# AD8336.net
KiCad netlist of a schematic drawn in EasyEDA Pro
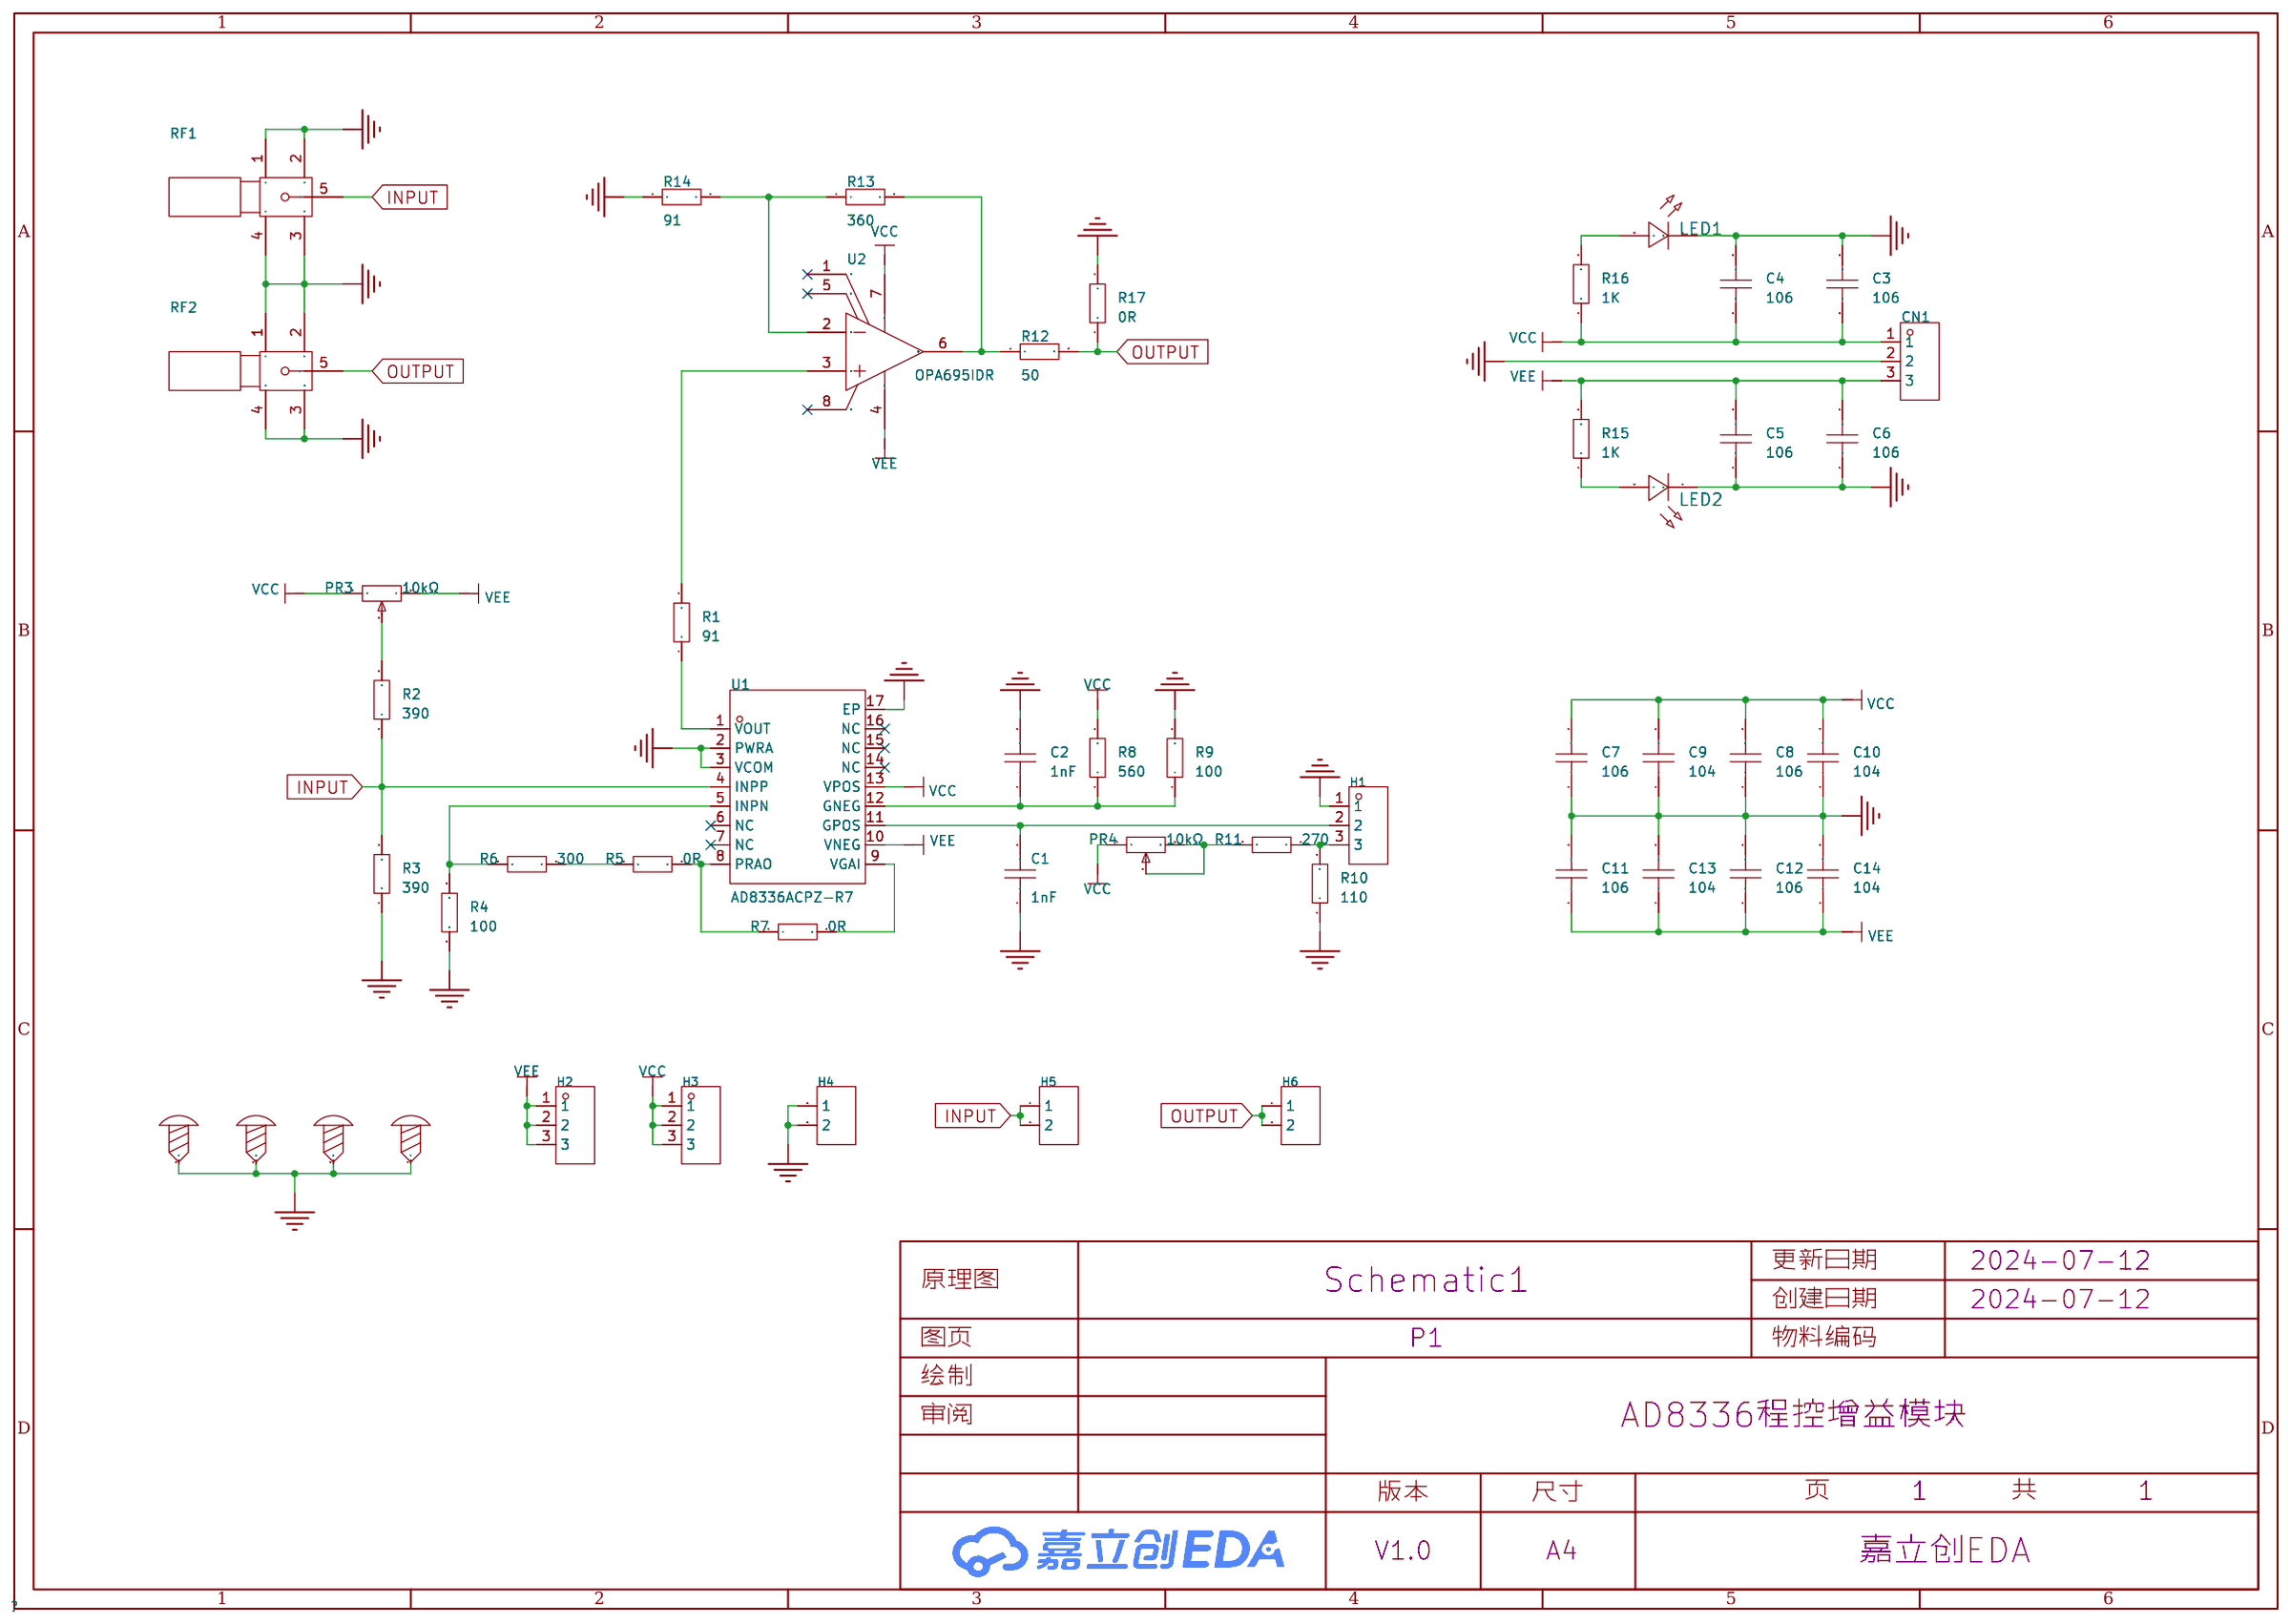
[diagram p0: schematic sheet]

(export (version "E")
  (design (tool "Eeschema 10.0.6"))
  (components
    (comp (ref "C1")
      (value "1nF")
      (footprint "easyedapro:C0603")
      (libsource (lib "easyedapro") (part "CapAcitance"))
    )
    (comp (ref "C2")
      (value "1nF")
      (footprint "easyedapro:C0603")
      (libsource (lib "easyedapro") (part "CapAcitance"))
    )
    (comp (ref "C3")
      (value "106")
      (footprint "easyedapro:C0603")
      (libsource (lib "easyedapro") (part "CapAcitance"))
    )
    (comp (ref "C4")
      (value "106")
      (footprint "easyedapro:C0603")
      (libsource (lib "easyedapro") (part "CapAcitance"))
    )
    (comp (ref "C5")
      (value "106")
      (footprint "easyedapro:C0603")
      (libsource (lib "easyedapro") (part "CapAcitance"))
    )
    (comp (ref "C6")
      (value "106")
      (footprint "easyedapro:C0603")
      (libsource (lib "easyedapro") (part "CapAcitance"))
    )
    (comp (ref "C7")
      (value "106")
      (footprint "easyedapro:C0603")
      (libsource (lib "easyedapro") (part "CapAcitance"))
    )
    (comp (ref "C8")
      (value "106")
      (footprint "easyedapro:C0603")
      (libsource (lib "easyedapro") (part "CapAcitance"))
    )
    (comp (ref "C9")
      (value "104")
      (footprint "easyedapro:C0603")
      (libsource (lib "easyedapro") (part "CapAcitance"))
    )
    (comp (ref "C10")
      (value "104")
      (footprint "easyedapro:C0603")
      (libsource (lib "easyedapro") (part "CapAcitance"))
    )
    (comp (ref "C11")
      (value "106")
      (footprint "easyedapro:C0603")
      (libsource (lib "easyedapro") (part "CapAcitance"))
    )
    (comp (ref "C12")
      (value "106")
      (footprint "easyedapro:C0603")
      (libsource (lib "easyedapro") (part "CapAcitance"))
    )
    (comp (ref "C13")
      (value "104")
      (footprint "easyedapro:C0603")
      (libsource (lib "easyedapro") (part "CapAcitance"))
    )
    (comp (ref "C14")
      (value "104")
      (footprint "easyedapro:C0603")
      (libsource (lib "easyedapro") (part "CapAcitance"))
    )
    (comp (ref "CN1")
      (value "MX301-5.0-03P-BU01-Cu-Y-A")
      (footprint "easyedapro:CONN-TH_3P-P5.0-MX301-5.0-03P-BU01-CU-Y-A")
      (fields (field (name "Manufacturer") "MAX(迈旭)"))
      (libsource (lib "easyedapro") (part "MX301-5.0-03P-BU01-CU-Y-A"))
    )
    (comp (ref "H1")
      (value "~")
      (footprint "easyedapro:HDR-TH_3P-P2.54-V-F")
      (libsource (lib "easyedapro") (part "PM254V-11-03-H85"))
    )
    (comp (ref "H2")
      (value "~")
      (footprint "easyedapro:HDR-TH_3P-P2.54-V-F")
      (libsource (lib "easyedapro") (part "PM254V-11-03-H85"))
    )
    (comp (ref "H3")
      (value "~")
      (footprint "easyedapro:HDR-TH_3P-P2.54-V-F")
      (libsource (lib "easyedapro") (part "PM254V-11-03-H85"))
    )
    (comp (ref "H4")
      (value "~")
      (footprint "easyedapro:HDR-TH_2P-P2.54-V-F")
      (libsource (lib "easyedapro") (part "Header-Female-2.54_1x2"))
    )
    (comp (ref "H5")
      (value "~")
      (footprint "easyedapro:HDR-TH_2P-P2.54-V-F")
      (libsource (lib "easyedapro") (part "Header-Female-2.54_1x2"))
    )
    (comp (ref "H6")
      (value "~")
      (footprint "easyedapro:HDR-TH_2P-P2.54-V-F")
      (libsource (lib "easyedapro") (part "Header-Female-2.54_1x2"))
    )
    (comp (ref "LED1")
      (value "~")
      (footprint "easyedapro:LED_0603")
      (libsource (lib "easyedapro") (part "LED_R"))
    )
    (comp (ref "LED2")
      (value "~")
      (footprint "easyedapro:LED_0603")
      (libsource (lib "easyedapro") (part "LED_R"))
    )
    (comp (ref "PR3")
      (value "10kΩ")
      (footprint "easyedapro:R_3296")
      (libsource (lib "easyedapro") (part "R_3296"))
    )
    (comp (ref "PR4")
      (value "10kΩ")
      (footprint "easyedapro:R_3296")
      (libsource (lib "easyedapro") (part "R_3296"))
    )
    (comp (ref "R1") (value "91") (footprint "easyedapro:R0603") (libsource (lib "easyedapro") (part "电阻")))
    (comp (ref "R2") (value "390") (footprint "easyedapro:R0603") (libsource (lib "easyedapro") (part "电阻")))
    (comp (ref "R3") (value "390") (footprint "easyedapro:R0603") (libsource (lib "easyedapro") (part "电阻")))
    (comp (ref "R4") (value "100") (footprint "easyedapro:R0603") (libsource (lib "easyedapro") (part "电阻")))
    (comp (ref "R5") (value "0R") (footprint "easyedapro:R0603") (libsource (lib "easyedapro") (part "电阻")))
    (comp (ref "R6") (value "300") (footprint "easyedapro:R0603") (libsource (lib "easyedapro") (part "电阻")))
    (comp (ref "R7") (value "0R") (footprint "easyedapro:R0603") (libsource (lib "easyedapro") (part "电阻")))
    (comp (ref "R8") (value "560") (footprint "easyedapro:R0603") (libsource (lib "easyedapro") (part "电阻")))
    (comp (ref "R9") (value "100") (footprint "easyedapro:R0603") (libsource (lib "easyedapro") (part "电阻")))
    (comp (ref "R10") (value "110") (footprint "easyedapro:R0603") (libsource (lib "easyedapro") (part "电阻")))
    (comp (ref "R11") (value "270") (footprint "easyedapro:R0603") (libsource (lib "easyedapro") (part "电阻")))
    (comp (ref "R12") (value "50") (footprint "easyedapro:R0603") (libsource (lib "easyedapro") (part "电阻")))
    (comp (ref "R13") (value "360") (footprint "easyedapro:R0603") (libsource (lib "easyedapro") (part "电阻")))
    (comp (ref "R14") (value "91") (footprint "easyedapro:R0603") (libsource (lib "easyedapro") (part "电阻")))
    (comp (ref "R15") (value "1K") (footprint "easyedapro:R0603") (libsource (lib "easyedapro") (part "电阻")))
    (comp (ref "R16") (value "1K") (footprint "easyedapro:R0603") (libsource (lib "easyedapro") (part "电阻")))
    (comp (ref "R17") (value "0R") (footprint "easyedapro:R0603") (libsource (lib "easyedapro") (part "电阻")))
    (comp (ref "RF1")
      (value "BWSMA-KE-Z001")
      (footprint "easyedapro:SMA-TH_BWSMA-KE-Z001")
      (fields (field (name "Manufacturer") "BAT WIRELESS(蝙蝠无线)"))
      (libsource (lib "easyedapro") (part "BWSMA-KE-Z001"))
    )
    (comp (ref "RF2")
      (value "BWSMA-KE-Z001")
      (footprint "easyedapro:SMA-TH_BWSMA-KE-Z001")
      (fields (field (name "Manufacturer") "BAT WIRELESS(蝙蝠无线)"))
      (libsource (lib "easyedapro") (part "BWSMA-KE-Z001"))
    )
    (comp (ref "TP1") (value "~") (footprint "easyedapro:M3螺丝") (libsource (lib "easyedapro") (part "螺丝孔")))
    (comp (ref "TP2") (value "~") (footprint "easyedapro:M3螺丝") (libsource (lib "easyedapro") (part "螺丝孔")))
    (comp (ref "TP3") (value "~") (footprint "easyedapro:M3螺丝") (libsource (lib "easyedapro") (part "螺丝孔")))
    (comp (ref "TP4") (value "~") (footprint "easyedapro:M3螺丝") (libsource (lib "easyedapro") (part "螺丝孔")))
    (comp (ref "U1")
      (value "AD8336ACPZ-R7")
      (footprint "easyedapro:LFCSP-16_L4.0-W4.0-P0.65-BL-EP2.2")
      (description "可变增益放大器-IC-信号处理-16-LFCSP-VQ（4x4）")
      (fields (field (name "Manufacturer") "ADI(亚德诺)"))
      (libsource (lib "easyedapro") (part "AD8336ACPZ-R7"))
    )
    (comp (ref "U2")
      (value "OPA695IDR")
      (footprint "easyedapro:SOIC-8_L5.0-W4.0-P1.27-LS6.1-BL")
      (description "放大器数:单路;增益带宽积(GBP):-;输入偏置电流(Ib):20uA;压摆率(SR):4300V/us;带宽(-3db):1.7GHz;")
      (fields (field (name "Manufacturer") "TI(德州仪器)"))
      (libsource (lib "easyedapro") (part "OPA695IDR"))
    )
  )
  (nets
    (net (code "1") (name "GND") (class "Default")
      (node (ref "C1") (pin "1") (pinfunction "1_1") (pintype "input"))
      (node (ref "C10") (pin "1") (pinfunction "1_1") (pintype "input"))
      (node (ref "C11") (pin "2") (pinfunction "2_2") (pintype "input"))
      (node (ref "C12") (pin "2") (pinfunction "2_2") (pintype "input"))
      (node (ref "C13") (pin "2") (pinfunction "2_2") (pintype "input"))
      (node (ref "C14") (pin "2") (pinfunction "2_2") (pintype "input"))
      (node (ref "C2") (pin "2") (pinfunction "2_2") (pintype "input"))
      (node (ref "C3") (pin "2") (pinfunction "2_2") (pintype "input"))
      (node (ref "C4") (pin "2") (pinfunction "2_2") (pintype "input"))
      (node (ref "C5") (pin "1") (pinfunction "1_1") (pintype "input"))
      (node (ref "C6") (pin "1") (pinfunction "1_1") (pintype "input"))
      (node (ref "C7") (pin "1") (pinfunction "1_1") (pintype "input"))
      (node (ref "C8") (pin "1") (pinfunction "1_1") (pintype "input"))
      (node (ref "C9") (pin "1") (pinfunction "1_1") (pintype "input"))
      (node (ref "CN1") (pin "2") (pinfunction "2_2") (pintype "unspecified"))
      (node (ref "H1") (pin "1") (pinfunction "1_1") (pintype "input"))
      (node (ref "H4") (pin "1") (pinfunction "1_1") (pintype "input"))
      (node (ref "H4") (pin "2") (pinfunction "2_2") (pintype "input"))
      (node (ref "LED1") (pin "1") (pinfunction "C_1") (pintype "input"))
      (node (ref "LED2") (pin "1") (pinfunction "C_1") (pintype "input"))
      (node (ref "R10") (pin "1") (pinfunction "1_1") (pintype "input"))
      (node (ref "R14") (pin "1") (pinfunction "1_1") (pintype "input"))
      (node (ref "R17") (pin "2") (pinfunction "2_2") (pintype "input"))
      (node (ref "R3") (pin "1") (pinfunction "1_1") (pintype "input"))
      (node (ref "R4") (pin "1") (pinfunction "1_1") (pintype "input"))
      (node (ref "R9") (pin "2") (pinfunction "2_2") (pintype "input"))
      (node (ref "RF1") (pin "1") (pinfunction "1_1") (pintype "unspecified"))
      (node (ref "RF1") (pin "2") (pinfunction "2_2") (pintype "unspecified"))
      (node (ref "RF1") (pin "3") (pinfunction "3_3") (pintype "unspecified"))
      (node (ref "RF1") (pin "4") (pinfunction "4_4") (pintype "unspecified"))
      (node (ref "RF2") (pin "1") (pinfunction "1_1") (pintype "unspecified"))
      (node (ref "RF2") (pin "2") (pinfunction "2_2") (pintype "unspecified"))
      (node (ref "RF2") (pin "3") (pinfunction "3_3") (pintype "unspecified"))
      (node (ref "RF2") (pin "4") (pinfunction "4_4") (pintype "unspecified"))
      (node (ref "TP1") (pin "1") (pinfunction "1_1") (pintype "input"))
      (node (ref "TP2") (pin "1") (pinfunction "1_1") (pintype "input"))
      (node (ref "TP3") (pin "1") (pinfunction "1_1") (pintype "input"))
      (node (ref "TP4") (pin "1") (pinfunction "1_1") (pintype "input"))
      (node (ref "U1") (pin "17") (pinfunction "EP_17") (pintype "unspecified"))
      (node (ref "U1") (pin "2") (pinfunction "PWRA_2") (pintype "unspecified"))
      (node (ref "U1") (pin "3") (pinfunction "VCOM_3") (pintype "unspecified"))
    )
    (net (code "2") (name "INPUT") (class "Default")
      (node (ref "H5") (pin "1") (pinfunction "1_1") (pintype "input"))
      (node (ref "H5") (pin "2") (pinfunction "2_2") (pintype "input"))
      (node (ref "R2") (pin "1") (pinfunction "1_1") (pintype "input"))
      (node (ref "R3") (pin "2") (pinfunction "2_2") (pintype "input"))
      (node (ref "RF1") (pin "5") (pinfunction "5_5") (pintype "unspecified"))
      (node (ref "U1") (pin "4") (pinfunction "INPP_4") (pintype "unspecified"))
    )
    (net (code "3") (name "Net-(H1-Pad3)") (class "Default")
      (node (ref "H1") (pin "3") (pinfunction "3_3") (pintype "input"))
      (node (ref "R10") (pin "2") (pinfunction "2_2") (pintype "input"))
      (node (ref "R11") (pin "1") (pinfunction "1_1") (pintype "input"))
    )
    (net (code "4") (name "Net-(LED1-A)") (class "Default")
      (node (ref "LED1") (pin "2") (pinfunction "A_2") (pintype "input"))
      (node (ref "R16") (pin "2") (pinfunction "2_2") (pintype "input"))
    )
    (net (code "5") (name "Net-(LED2-A)") (class "Default")
      (node (ref "LED2") (pin "2") (pinfunction "A_2") (pintype "input"))
      (node (ref "R15") (pin "1") (pinfunction "1_1") (pintype "input"))
    )
    (net (code "6") (name "Net-(PR3-Pad2)") (class "Default")
      (node (ref "PR3") (pin "2") (pinfunction "2_2") (pintype "input"))
      (node (ref "R2") (pin "2") (pinfunction "2_2") (pintype "input"))
    )
    (net (code "7") (name "Net-(PR4-Pad2)") (class "Default")
      (node (ref "PR4") (pin "2") (pinfunction "2_2") (pintype "input"))
      (node (ref "PR4") (pin "3") (pinfunction "3_3") (pintype "input"))
      (node (ref "R11") (pin "2") (pinfunction "2_2") (pintype "input"))
    )
    (net (code "8") (name "Net-(R5-Pad1)") (class "Default")
      (node (ref "R5") (pin "1") (pinfunction "1_1") (pintype "input"))
      (node (ref "R6") (pin "2") (pinfunction "2_2") (pintype "input"))
    )
    (net (code "9") (name "Net-(U1-GNEG)") (class "Default")
      (node (ref "C2") (pin "1") (pinfunction "1_1") (pintype "input"))
      (node (ref "R8") (pin "1") (pinfunction "1_1") (pintype "input"))
      (node (ref "R9") (pin "1") (pinfunction "1_1") (pintype "input"))
      (node (ref "U1") (pin "12") (pinfunction "GNEG_12") (pintype "unspecified"))
    )
    (net (code "10") (name "Net-(U1-GPOS)") (class "Default")
      (node (ref "C1") (pin "2") (pinfunction "2_2") (pintype "input"))
      (node (ref "H1") (pin "2") (pinfunction "2_2") (pintype "input"))
      (node (ref "U1") (pin "11") (pinfunction "GPOS_11") (pintype "unspecified"))
    )
    (net (code "11") (name "Net-(U1-INPN)") (class "Default")
      (node (ref "R4") (pin "2") (pinfunction "2_2") (pintype "input"))
      (node (ref "R6") (pin "1") (pinfunction "1_1") (pintype "input"))
      (node (ref "U1") (pin "5") (pinfunction "INPN_5") (pintype "unspecified"))
    )
    (net (code "12") (name "Net-(U1-PRAO)") (class "Default")
      (node (ref "R5") (pin "2") (pinfunction "2_2") (pintype "input"))
      (node (ref "R7") (pin "1") (pinfunction "1_1") (pintype "input"))
      (node (ref "U1") (pin "8") (pinfunction "PRAO_8") (pintype "unspecified"))
    )
    (net (code "13") (name "Net-(U1-VGAI)") (class "Default")
      (node (ref "R7") (pin "2") (pinfunction "2_2") (pintype "input"))
      (node (ref "U1") (pin "9") (pinfunction "VGAI_9") (pintype "unspecified"))
    )
    (net (code "14") (name "Net-(U1-VOUT)") (class "Default")
      (node (ref "R1") (pin "1") (pinfunction "1_1") (pintype "input"))
      (node (ref "U1") (pin "1") (pinfunction "VOUT_1") (pintype "unspecified"))
    )
    (net (code "15") (name "Net-(U2-+IN)") (class "Default")
      (node (ref "R1") (pin "2") (pinfunction "2_2") (pintype "input"))
      (node (ref "U2") (pin "3") (pinfunction "+IN_3") (pintype "unspecified"))
    )
    (net (code "16") (name "Net-(U2--IN)") (class "Default")
      (node (ref "R13") (pin "1") (pinfunction "1_1") (pintype "input"))
      (node (ref "R14") (pin "2") (pinfunction "2_2") (pintype "input"))
      (node (ref "U2") (pin "2") (pinfunction "-IN_2") (pintype "unspecified"))
    )
    (net (code "17") (name "Net-(U2-Output)") (class "Default")
      (node (ref "R12") (pin "1") (pinfunction "1_1") (pintype "input"))
      (node (ref "R13") (pin "2") (pinfunction "2_2") (pintype "input"))
      (node (ref "U2") (pin "6") (pinfunction "Output_6") (pintype "output"))
    )
    (net (code "18") (name "OUTPUT") (class "Default")
      (node (ref "H6") (pin "1") (pinfunction "1_1") (pintype "input"))
      (node (ref "H6") (pin "2") (pinfunction "2_2") (pintype "input"))
      (node (ref "R12") (pin "2") (pinfunction "2_2") (pintype "input"))
      (node (ref "R17") (pin "1") (pinfunction "1_1") (pintype "input"))
      (node (ref "RF2") (pin "5") (pinfunction "5_5") (pintype "unspecified"))
    )
    (net (code "19") (name "VCC") (class "Default")
      (node (ref "C10") (pin "2") (pinfunction "2_2") (pintype "input"))
      (node (ref "C3") (pin "1") (pinfunction "1_1") (pintype "input"))
      (node (ref "C4") (pin "1") (pinfunction "1_1") (pintype "input"))
      (node (ref "C7") (pin "2") (pinfunction "2_2") (pintype "input"))
      (node (ref "C8") (pin "2") (pinfunction "2_2") (pintype "input"))
      (node (ref "C9") (pin "2") (pinfunction "2_2") (pintype "input"))
      (node (ref "CN1") (pin "1") (pinfunction "1_1") (pintype "unspecified"))
      (node (ref "H3") (pin "1") (pinfunction "1_1") (pintype "input"))
      (node (ref "H3") (pin "2") (pinfunction "2_2") (pintype "input"))
      (node (ref "H3") (pin "3") (pinfunction "3_3") (pintype "input"))
      (node (ref "PR3") (pin "1") (pinfunction "1_1") (pintype "input"))
      (node (ref "PR4") (pin "1") (pinfunction "1_1") (pintype "input"))
      (node (ref "R16") (pin "1") (pinfunction "1_1") (pintype "input"))
      (node (ref "R8") (pin "2") (pinfunction "2_2") (pintype "input"))
      (node (ref "U1") (pin "13") (pinfunction "VPOS_13") (pintype "unspecified"))
      (node (ref "U2") (pin "7") (pinfunction "+VS_7") (pintype "unspecified"))
    )
    (net (code "20") (name "VEE") (class "Default")
      (node (ref "C11") (pin "1") (pinfunction "1_1") (pintype "input"))
      (node (ref "C12") (pin "1") (pinfunction "1_1") (pintype "input"))
      (node (ref "C13") (pin "1") (pinfunction "1_1") (pintype "input"))
      (node (ref "C14") (pin "1") (pinfunction "1_1") (pintype "input"))
      (node (ref "C5") (pin "2") (pinfunction "2_2") (pintype "input"))
      (node (ref "C6") (pin "2") (pinfunction "2_2") (pintype "input"))
      (node (ref "CN1") (pin "3") (pinfunction "3_3") (pintype "unspecified"))
      (node (ref "H2") (pin "1") (pinfunction "1_1") (pintype "input"))
      (node (ref "H2") (pin "2") (pinfunction "2_2") (pintype "input"))
      (node (ref "H2") (pin "3") (pinfunction "3_3") (pintype "input"))
      (node (ref "PR3") (pin "3") (pinfunction "3_3") (pintype "input"))
      (node (ref "R15") (pin "2") (pinfunction "2_2") (pintype "input"))
      (node (ref "U1") (pin "10") (pinfunction "VNEG_10") (pintype "unspecified"))
      (node (ref "U2") (pin "4") (pinfunction "-VS_4") (pintype "unspecified"))
    )
    (net (code "21") (name "unconnected-(U1-NC-Pad6)") (class "Default")
      (node (ref "U1") (pin "6") (pinfunction "NC_6") (pintype "unspecified+no_connect"))
    )
    (net (code "22") (name "unconnected-(U1-NC-Pad7)") (class "Default")
      (node (ref "U1") (pin "7") (pinfunction "NC_7") (pintype "unspecified+no_connect"))
    )
    (net (code "23") (name "unconnected-(U1-NC-Pad14)") (class "Default")
      (node (ref "U1") (pin "14") (pinfunction "NC_14") (pintype "unspecified+no_connect"))
    )
    (net (code "24") (name "unconnected-(U1-NC-Pad15)") (class "Default")
      (node (ref "U1") (pin "15") (pinfunction "NC_15") (pintype "unspecified+no_connect"))
    )
    (net (code "25") (name "unconnected-(U1-NC-Pad16)") (class "Default")
      (node (ref "U1") (pin "16") (pinfunction "NC_16") (pintype "unspecified+no_connect"))
    )
    (net (code "26") (name "unconnected-(U2-DIS#-Pad8)") (class "Default")
      (node (ref "U2") (pin "8") (pinfunction "DIS#_8") (pintype "unspecified+no_connect"))
    )
    (net (code "27") (name "unconnected-(U2-NC-Pad1)") (class "Default")
      (node (ref "U2") (pin "1") (pinfunction "NC_1") (pintype "unspecified+no_connect"))
    )
    (net (code "28") (name "unconnected-(U2-NC-Pad5)") (class "Default")
      (node (ref "U2") (pin "5") (pinfunction "NC_5") (pintype "unspecified+no_connect"))
    )
  )
)
